# Schematic.net
KiCad netlist of a schematic drawn in EAGLE
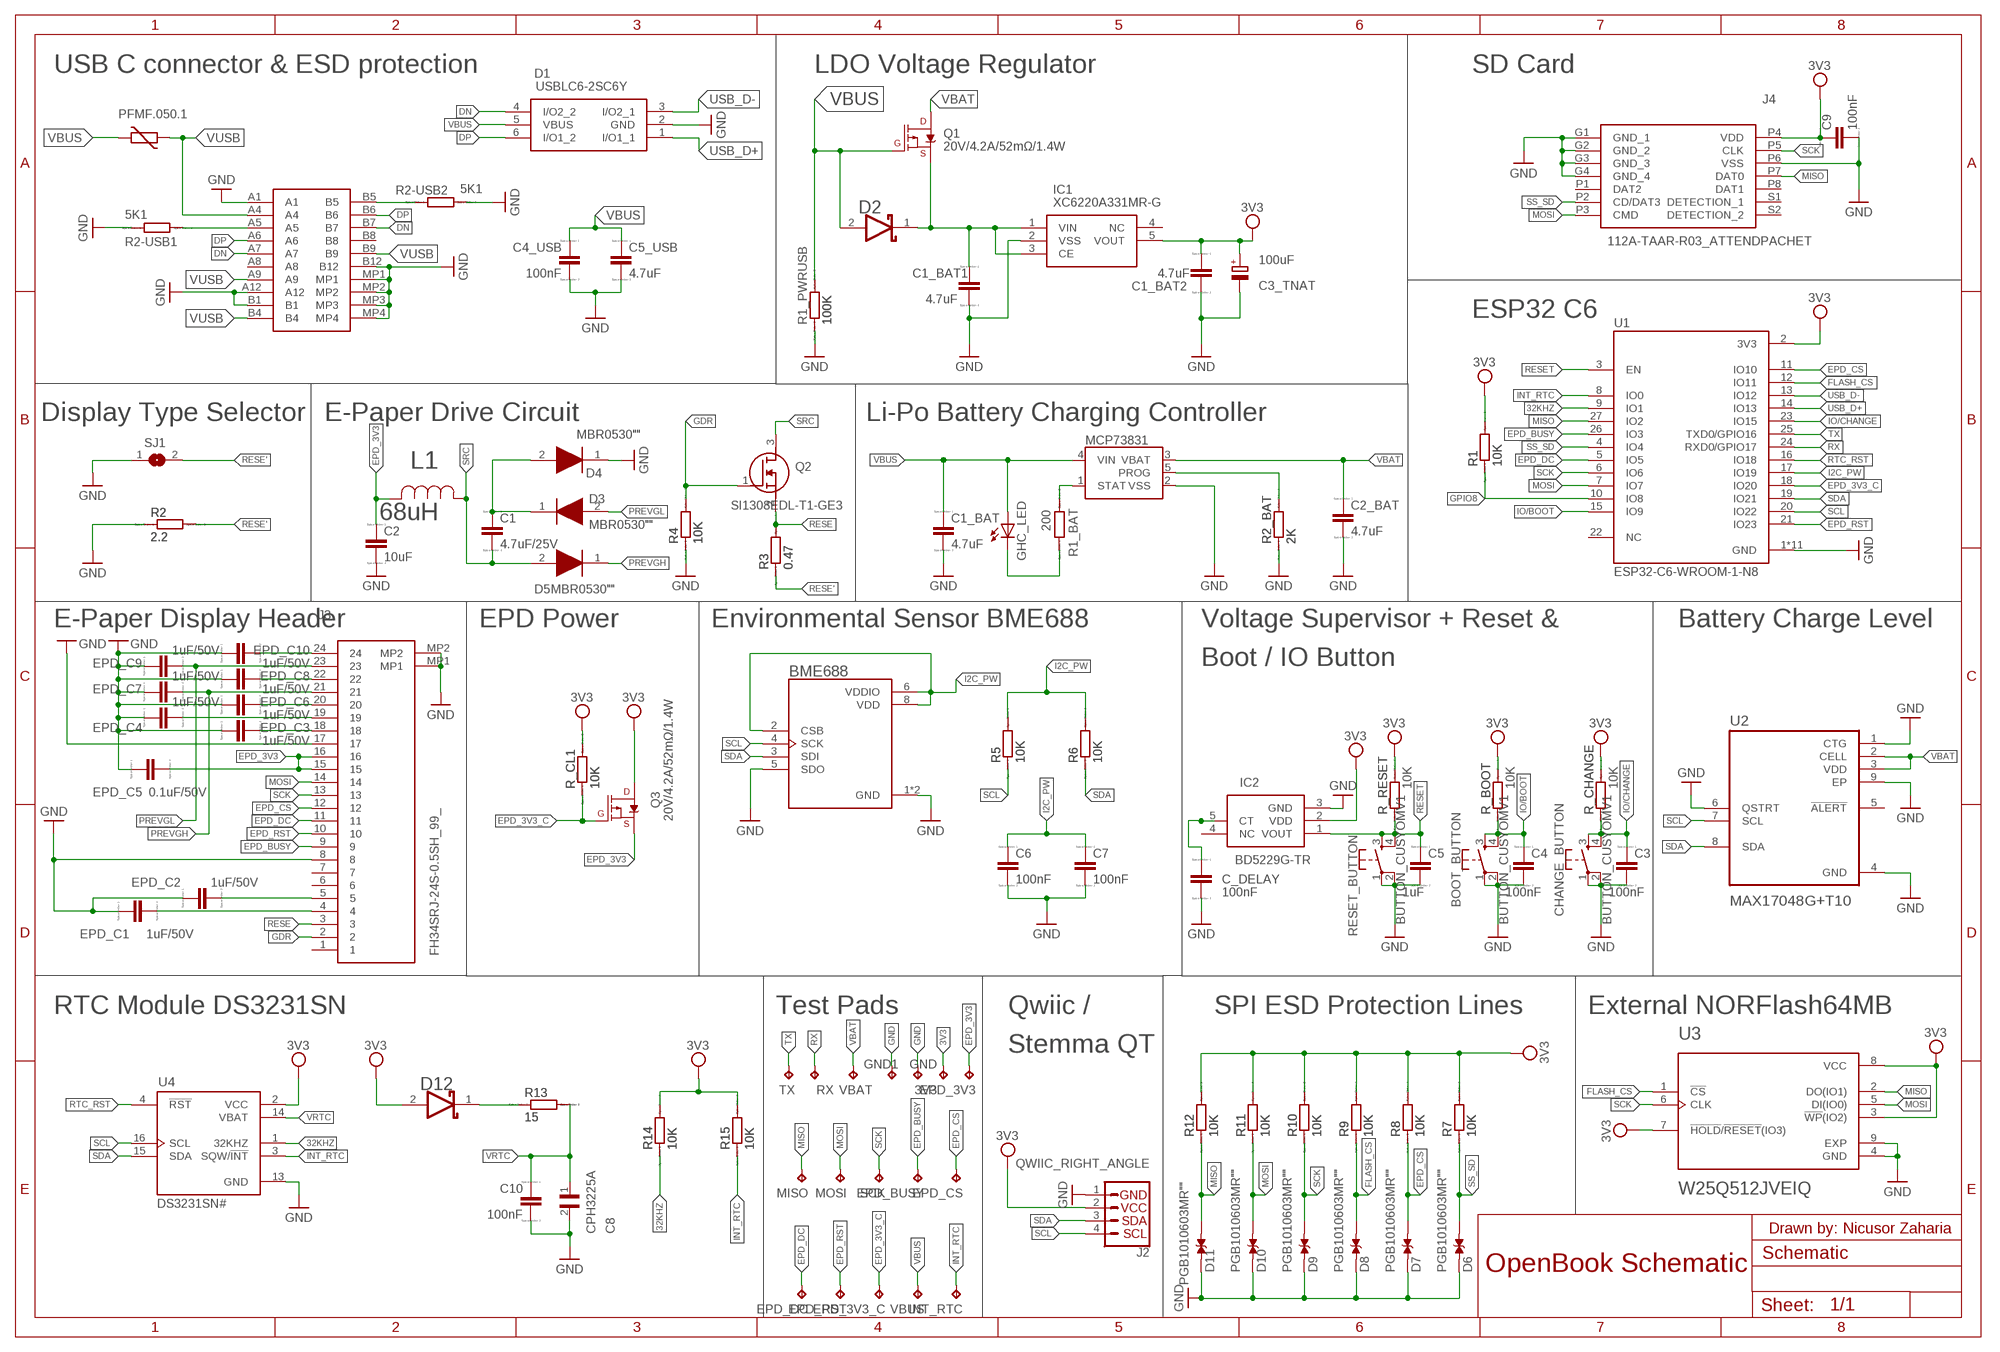
[diagram p0: schematic, sheet 1]

(export (version "E")
  (design (tool "Eeschema 10.0.6"))
  (components
    (comp (ref "3V3")
      (value "TPTP20R")
      (footprint "eagle-import:TP20R")
      (libsource (lib "eagle-import") (part "TPTP20R"))
    )
    (comp (ref "BME688")
      (value "ESP32_WROVER_BME680_BME680")
      (footprint "eagle-import:ESP32_WROVER_BME680_PSON80P300X300X100-8N")
      (fields (field (name "MF") "Bosch Sensortec") (field (name "MP") "BME680"))
      (libsource (lib "eagle-import") (part "ESP32_WROVER_BME680_BME680"))
    )
    (comp (ref "BOOT_BUTTON")
      (value "BUTTON_CUSYOMV1")
      (footprint "eagle-import:MYBUTTON")
      (libsource (lib "eagle-import") (part "BUTTON_CUSYOMV1MINE"))
    )
    (comp (ref "C1")
      (value "4.7uF/25V")
      (footprint "eagle-import:EAGLE-LTSPICE_C0402")
      (libsource (lib "eagle-import") (part "EAGLE-LTSPICE_CC0402"))
    )
    (comp (ref "C1_BAT")
      (value "4.7uF")
      (footprint "eagle-import:EAGLE-LTSPICE_C0402")
      (libsource (lib "eagle-import") (part "EAGLE-LTSPICE_CC0402"))
    )
    (comp (ref "C1_BAT1")
      (value "4.7uF")
      (footprint "eagle-import:EAGLE-LTSPICE_C0402")
      (libsource (lib "eagle-import") (part "EAGLE-LTSPICE_CC0402"))
    )
    (comp (ref "C1_BAT2")
      (value "4.7uF")
      (footprint "eagle-import:EAGLE-LTSPICE_C0402")
      (libsource (lib "eagle-import") (part "EAGLE-LTSPICE_CC0402"))
    )
    (comp (ref "C2")
      (value "10uF")
      (footprint "eagle-import:EAGLE-LTSPICE_C0402")
      (libsource (lib "eagle-import") (part "EAGLE-LTSPICE_CC0402"))
    )
    (comp (ref "C2_BAT")
      (value "4.7uF")
      (footprint "eagle-import:EAGLE-LTSPICE_C0402")
      (libsource (lib "eagle-import") (part "EAGLE-LTSPICE_CC0402"))
    )
    (comp (ref "C3")
      (value "100nF")
      (footprint "eagle-import:EAGLE-LTSPICE_C0402")
      (libsource (lib "eagle-import") (part "EAGLE-LTSPICE_CC0402"))
    )
    (comp (ref "C3_TNAT")
      (value "100uF")
      (footprint "eagle-import:RCL_CT3528")
      (libsource (lib "eagle-import") (part "RCL_CPOL-EUCT3528"))
    )
    (comp (ref "C4")
      (value "100nF")
      (footprint "eagle-import:EAGLE-LTSPICE_C0402")
      (libsource (lib "eagle-import") (part "EAGLE-LTSPICE_CC0402"))
    )
    (comp (ref "C4_USB")
      (value "100nF")
      (footprint "eagle-import:EAGLE-LTSPICE_C0402")
      (libsource (lib "eagle-import") (part "EAGLE-LTSPICE_CC0402"))
    )
    (comp (ref "C5")
      (value "1uF")
      (footprint "eagle-import:EAGLE-LTSPICE_C0402")
      (libsource (lib "eagle-import") (part "EAGLE-LTSPICE_CC0402"))
    )
    (comp (ref "C5_USB")
      (value "4.7uF")
      (footprint "eagle-import:EAGLE-LTSPICE_C0402")
      (libsource (lib "eagle-import") (part "EAGLE-LTSPICE_CC0402"))
    )
    (comp (ref "C6")
      (value "100nF")
      (footprint "eagle-import:EAGLE-LTSPICE_C0402")
      (libsource (lib "eagle-import") (part "EAGLE-LTSPICE_CC0402"))
    )
    (comp (ref "C7")
      (value "100nF")
      (footprint "eagle-import:EAGLE-LTSPICE_C0402")
      (libsource (lib "eagle-import") (part "EAGLE-LTSPICE_CC0402"))
    )
    (comp (ref "C8")
      (value "CPH3225A")
      (footprint "eagle-import:CAPCP3225X100N")
      (fields (field (name "MF") "Seiko Instruments"))
      (libsource (lib "eagle-import") (part "CPH3225A"))
    )
    (comp (ref "C9")
      (value "100nF")
      (footprint "eagle-import:EAGLE-LTSPICE_C0402")
      (libsource (lib "eagle-import") (part "EAGLE-LTSPICE_CC0402"))
    )
    (comp (ref "C10")
      (value "100nF")
      (footprint "eagle-import:EAGLE-LTSPICE_C0402")
      (libsource (lib "eagle-import") (part "EAGLE-LTSPICE_CC0402"))
    )
    (comp (ref "CHANGE_BUTTON")
      (value "BUTTON_CUSYOMV1")
      (footprint "eagle-import:MYBUTTON")
      (libsource (lib "eagle-import") (part "BUTTON_CUSYOMV1MINE"))
    )
    (comp (ref "C_DELAY")
      (value "100nF")
      (footprint "eagle-import:EAGLE-LTSPICE_C0402")
      (libsource (lib "eagle-import") (part "EAGLE-LTSPICE_CC0402"))
    )
    (comp (ref "D1")
      (value "USBLC6-2SC6Y")
      (footprint "eagle-import:SOT95P280X145-6N")
      (fields (field (name "MF") "STMicroelectronics"))
      (libsource (lib "eagle-import") (part "USBLC6-2SC6Y"))
    )
    (comp (ref "D2")
      (value "ESP32_WROVER_AVX---SD0805S020S1R0_AVX_SD0805S020S1R0_0_0AVX_SD0805S020S1R0_0_0")
      (footprint "eagle-import:ESP32_WROVER_AVX---SD0805S020S1R0_AVX_SD0805S020S1R0_0")
      (fields
        (field (name "DIGIKEY_PART_NUMBER") "478-7800-1-ND")
        (field (name "MF") "AVX")
        (field (name "MOUSER_PART_NUMBER") "581-SD0805S020S1R0")
      )
      (libsource (lib "eagle-import") (part "ESP32_WROVER_AVX---SD0805S020S1R0_AVX_SD0805S020S1R0_0_0AVX_SD0805S020S1R0_0_0"))
    )
    (comp (ref "D3")
      (value "MBR0530\"\"")
      (footprint "eagle-import:SOD3716X135N")
      (libsource (lib "eagle-import") (part "MBR0530{dblquote}{dblquote}"))
    )
    (comp (ref "D4")
      (value "MBR0530\"\"")
      (footprint "eagle-import:SOD3716X135N")
      (libsource (lib "eagle-import") (part "MBR0530{dblquote}{dblquote}"))
    )
    (comp (ref "D5")
      (value "MBR0530\"\"")
      (footprint "eagle-import:SOD3716X135N")
      (libsource (lib "eagle-import") (part "MBR0530{dblquote}{dblquote}"))
    )
    (comp (ref "D6")
      (value "PGB1010603MR\"\"")
      (footprint "eagle-import:DIOC1608X36N")
      (libsource (lib "eagle-import") (part "PGB1010603MR{dblquote}{dblquote}"))
    )
    (comp (ref "D7")
      (value "PGB1010603MR\"\"")
      (footprint "eagle-import:DIOC1608X36N")
      (libsource (lib "eagle-import") (part "PGB1010603MR{dblquote}{dblquote}"))
    )
    (comp (ref "D8")
      (value "PGB1010603MR\"\"")
      (footprint "eagle-import:DIOC1608X36N")
      (libsource (lib "eagle-import") (part "PGB1010603MR{dblquote}{dblquote}"))
    )
    (comp (ref "D9")
      (value "PGB1010603MR\"\"")
      (footprint "eagle-import:DIOC1608X36N")
      (libsource (lib "eagle-import") (part "PGB1010603MR{dblquote}{dblquote}"))
    )
    (comp (ref "D10")
      (value "PGB1010603MR\"\"")
      (footprint "eagle-import:DIOC1608X36N")
      (libsource (lib "eagle-import") (part "PGB1010603MR{dblquote}{dblquote}"))
    )
    (comp (ref "D11")
      (value "PGB1010603MR\"\"")
      (footprint "eagle-import:DIOC1608X36N")
      (libsource (lib "eagle-import") (part "PGB1010603MR{dblquote}{dblquote}"))
    )
    (comp (ref "D12")
      (value "ESP32_WROVER_AVX---SD0805S020S1R0_AVX_SD0805S020S1R0_0_0AVX_SD0805S020S1R0_0_0")
      (footprint "eagle-import:ESP32_WROVER_AVX---SD0805S020S1R0_AVX_SD0805S020S1R0_0")
      (fields
        (field (name "DIGIKEY_PART_NUMBER") "478-7800-1-ND")
        (field (name "MF") "AVX")
        (field (name "MOUSER_PART_NUMBER") "581-SD0805S020S1R0")
      )
      (libsource (lib "eagle-import") (part "ESP32_WROVER_AVX---SD0805S020S1R0_AVX_SD0805S020S1R0_0_0AVX_SD0805S020S1R0_0_0"))
    )
    (comp (ref "EPD_3V3")
      (value "TPTP20R")
      (footprint "eagle-import:TP20R")
      (libsource (lib "eagle-import") (part "TPTP20R"))
    )
    (comp (ref "EPD_3V3_C")
      (value "TPTP20R")
      (footprint "eagle-import:TP20R")
      (libsource (lib "eagle-import") (part "TPTP20R"))
    )
    (comp (ref "EPD_BUSY")
      (value "TPTP20R")
      (footprint "eagle-import:TP20R")
      (libsource (lib "eagle-import") (part "TPTP20R"))
    )
    (comp (ref "EPD_C1")
      (value "1uF/50V")
      (footprint "eagle-import:EAGLE-LTSPICE_C0402")
      (libsource (lib "eagle-import") (part "EAGLE-LTSPICE_CC0402"))
    )
    (comp (ref "EPD_C2")
      (value "1uF/50V")
      (footprint "eagle-import:EAGLE-LTSPICE_C0402")
      (libsource (lib "eagle-import") (part "EAGLE-LTSPICE_CC0402"))
    )
    (comp (ref "EPD_C3")
      (value "1uF/50V")
      (footprint "eagle-import:EAGLE-LTSPICE_C0402")
      (libsource (lib "eagle-import") (part "EAGLE-LTSPICE_CC0402"))
    )
    (comp (ref "EPD_C4")
      (value "1uF/50V")
      (footprint "eagle-import:EAGLE-LTSPICE_C0402")
      (libsource (lib "eagle-import") (part "EAGLE-LTSPICE_CC0402"))
    )
    (comp (ref "EPD_C5")
      (value "0.1uF/50V")
      (footprint "eagle-import:EAGLE-LTSPICE_C0402")
      (libsource (lib "eagle-import") (part "EAGLE-LTSPICE_CC0402"))
    )
    (comp (ref "EPD_C6")
      (value "1uF/50V")
      (footprint "eagle-import:EAGLE-LTSPICE_C0402")
      (libsource (lib "eagle-import") (part "EAGLE-LTSPICE_CC0402"))
    )
    (comp (ref "EPD_C7")
      (value "1uF/50V")
      (footprint "eagle-import:EAGLE-LTSPICE_C0402")
      (libsource (lib "eagle-import") (part "EAGLE-LTSPICE_CC0402"))
    )
    (comp (ref "EPD_C8")
      (value "1uF/50V")
      (footprint "eagle-import:EAGLE-LTSPICE_C0402")
      (libsource (lib "eagle-import") (part "EAGLE-LTSPICE_CC0402"))
    )
    (comp (ref "EPD_C9")
      (value "1uF/50V")
      (footprint "eagle-import:EAGLE-LTSPICE_C0402")
      (libsource (lib "eagle-import") (part "EAGLE-LTSPICE_CC0402"))
    )
    (comp (ref "EPD_C10")
      (value "1uF/50V")
      (footprint "eagle-import:EAGLE-LTSPICE_C0402")
      (libsource (lib "eagle-import") (part "EAGLE-LTSPICE_CC0402"))
    )
    (comp (ref "EPD_CS")
      (value "TPTP20R")
      (footprint "eagle-import:TP20R")
      (libsource (lib "eagle-import") (part "TPTP20R"))
    )
    (comp (ref "EPD_DC")
      (value "TPTP20R")
      (footprint "eagle-import:TP20R")
      (libsource (lib "eagle-import") (part "TPTP20R"))
    )
    (comp (ref "EPD_RST")
      (value "TPTP20R")
      (footprint "eagle-import:TP20R")
      (libsource (lib "eagle-import") (part "TPTP20R"))
    )
    (comp (ref "GHC_LED")
      (value "ADAFRUIT_LEDCHIP-LED0603")
      (footprint "eagle-import:ADAFRUIT_CHIP-LED0603")
      (libsource (lib "eagle-import") (part "ADAFRUIT_LEDCHIP-LED0603"))
    )
    (comp (ref "GND")
      (value "TPTP20R")
      (footprint "eagle-import:TP20R")
      (libsource (lib "eagle-import") (part "TPTP20R"))
    )
    (comp (ref "GND1")
      (value "TPTP20R")
      (footprint "eagle-import:TP20R")
      (libsource (lib "eagle-import") (part "TPTP20R"))
    )
    (comp (ref "IC1")
      (value "XC6220A331MR-G")
      (footprint "eagle-import:SOT95P280X120-5N")
      (fields (field (name "MOUSER_PART_NUMBER") "865-XC6220A331MR-G"))
      (libsource (lib "eagle-import") (part "XC6220A331MR-G"))
    )
    (comp (ref "IC2")
      (value "BD5229G-TR")
      (footprint "eagle-import:SOT95P280X125-5N")
      (fields (field (name "MOUSER_PART_NUMBER") "755-BD5229G-TR"))
      (libsource (lib "eagle-import") (part "BD5229G-TR"))
    )
    (comp (ref "INT_RTC")
      (value "TPTP20R")
      (footprint "eagle-import:TP20R")
      (libsource (lib "eagle-import") (part "TPTP20R"))
    )
    (comp (ref "J1")
      (value "SAMACSYS_PARTS_USB4110-GF-A")
      (footprint "eagle-import:SAMACSYS_PARTS_USB4110GFA")
      (fields
        (field (name "MANUFACTURER_PART_NUMBER") "USB4110-GF-A")
        (field (name "MOUSER_PART_NUMBER") "640-USB4110-GF-A")
      )
      (libsource (lib "eagle-import") (part "SAMACSYS_PARTS_USB4110-GF-A"))
    )
    (comp (ref "J2")
      (value "QWIIC_RIGHT_ANGLE")
      (footprint "eagle-import:JST04_1MM_RA")
      (libsource (lib "eagle-import") (part "QWIIC_CONNECTORJS-1MM"))
    )
    (comp (ref "J3")
      (value "FH34SRJ-24S-0.5SH_99_")
      (footprint "eagle-import:FH34SRJ24S05SH99")
      (fields
        (field (name "MANUFACTURER_PART_NUMBER") "FH34SRJ-24S-0.5SH(99)")
        (field (name "MOUSER_PART_NUMBER") "798-FH34SRJ24S05SH99")
      )
      (libsource (lib "eagle-import") (part "FH34SRJ-24S-0.5SH_99_"))
    )
    (comp (ref "J4")
      (value "112A-TAAR-R03_ATTENDPACHET")
      (footprint "eagle-import:112ATAARR03ATTEND")
      (libsource (lib "eagle-import") (part "112A-TAAR-R03_ATTENDPACHET"))
    )
    (comp (ref "L1")
      (value "68uH")
      (footprint "eagle-import:IND_4828-WE-TPC_WRE")
      (fields
        (field (name "MANUFACTURER_PART_NUMBER") "744043680")
        (field (name "COPYRIGHT") "Copyright (C) 2024 Ultra Librarian. All rights reserved.")
      )
      (libsource (lib "eagle-import") (part "744043680IND_4828-WE-TPC_WRE"))
    )
    (comp (ref "MCP73831")
      (value "ESP32_WROVER_SPARKFUN-IC-POWER_MCP73831")
      (footprint "eagle-import:ESP32_WROVER_SPARKFUN-IC-POWER_SOT23-5")
      (libsource (lib "eagle-import") (part "ESP32_WROVER_SPARKFUN-IC-POWER_MCP73831"))
    )
    (comp (ref "MISO")
      (value "TPTP20R")
      (footprint "eagle-import:TP20R")
      (libsource (lib "eagle-import") (part "TPTP20R"))
    )
    (comp (ref "MOSI")
      (value "TPTP20R")
      (footprint "eagle-import:TP20R")
      (libsource (lib "eagle-import") (part "TPTP20R"))
    )
    (comp (ref "PFMF.050.1")
      (value "ESP32C6_VARISTORCN1812")
      (footprint "eagle-import:ESP32C6_VARISTOR_CT_CN1812")
      (libsource (lib "eagle-import") (part "ESP32C6_VARISTORCN1812"))
    )
    (comp (ref "Q1")
      (value "20V/4.2A/52mΩ/1.4W")
      (footprint "eagle-import:ESP32_WROVER_SPARKFUN-DISCRETESEMI_SOT23-3")
      (libsource (lib "eagle-import") (part "ESP32_WROVER_SPARKFUN-DISCRETESEMI_MOSFET_PCH-DMG2305UX-7"))
    )
    (comp (ref "Q2")
      (value "SI1308EDL-T1-GE3")
      (footprint "eagle-import:SOT65P210X110-3N")
      (fields (field (name "MF") "Vishay Siliconix"))
      (libsource (lib "eagle-import") (part "SI1308EDL-T1-GE3"))
    )
    (comp (ref "Q3")
      (value "20V/4.2A/52mΩ/1.4W")
      (footprint "eagle-import:ESP32_WROVER_SPARKFUN-DISCRETESEMI_SOT23-3")
      (libsource (lib "eagle-import") (part "ESP32_WROVER_SPARKFUN-DISCRETESEMI_MOSFET_PCH-DMG2305UX-7"))
    )
    (comp (ref "R1")
      (value "10K")
      (footprint "eagle-import:ESP32_WROVER_EAGLE-LTSPICE_R0402")
      (libsource (lib "eagle-import") (part "ESP32_WROVER_EAGLE-LTSPICE_R"))
    )
    (comp (ref "R1_BAT")
      (value "200")
      (footprint "eagle-import:ESP32_WROVER_EAGLE-LTSPICE_R0402")
      (libsource (lib "eagle-import") (part "ESP32_WROVER_EAGLE-LTSPICE_R"))
    )
    (comp (ref "R1_PWRUSB")
      (value "100K")
      (footprint "eagle-import:ESP32_WROVER_EAGLE-LTSPICE_R0402")
      (libsource (lib "eagle-import") (part "ESP32_WROVER_EAGLE-LTSPICE_R"))
    )
    (comp (ref "R2")
      (value "2.2")
      (footprint "eagle-import:ESP32_WROVER_EAGLE-LTSPICE_R0402")
      (libsource (lib "eagle-import") (part "ESP32_WROVER_EAGLE-LTSPICE_R"))
    )
    (comp (ref "R2-USB1")
      (value "5K1")
      (footprint "eagle-import:ESP32_WROVER_EAGLE-LTSPICE_R0402")
      (libsource (lib "eagle-import") (part "ESP32_WROVER_EAGLE-LTSPICE_R"))
    )
    (comp (ref "R2-USB2")
      (value "5K1")
      (footprint "eagle-import:ESP32_WROVER_EAGLE-LTSPICE_R0402")
      (libsource (lib "eagle-import") (part "ESP32_WROVER_EAGLE-LTSPICE_R"))
    )
    (comp (ref "R2_BAT")
      (value "2K")
      (footprint "eagle-import:ESP32_WROVER_EAGLE-LTSPICE_R0402")
      (libsource (lib "eagle-import") (part "ESP32_WROVER_EAGLE-LTSPICE_R"))
    )
    (comp (ref "R3")
      (value "0.47")
      (footprint "eagle-import:ESP32_WROVER_EAGLE-LTSPICE_R0402")
      (libsource (lib "eagle-import") (part "ESP32_WROVER_EAGLE-LTSPICE_R"))
    )
    (comp (ref "R4")
      (value "10K")
      (footprint "eagle-import:ESP32_WROVER_EAGLE-LTSPICE_R0402")
      (libsource (lib "eagle-import") (part "ESP32_WROVER_EAGLE-LTSPICE_R"))
    )
    (comp (ref "R5")
      (value "10K")
      (footprint "eagle-import:ESP32_WROVER_EAGLE-LTSPICE_R0402")
      (libsource (lib "eagle-import") (part "ESP32_WROVER_EAGLE-LTSPICE_R"))
    )
    (comp (ref "R6")
      (value "10K")
      (footprint "eagle-import:ESP32_WROVER_EAGLE-LTSPICE_R0402")
      (libsource (lib "eagle-import") (part "ESP32_WROVER_EAGLE-LTSPICE_R"))
    )
    (comp (ref "R7")
      (value "10K")
      (footprint "eagle-import:ESP32_WROVER_EAGLE-LTSPICE_R0402")
      (libsource (lib "eagle-import") (part "ESP32_WROVER_EAGLE-LTSPICE_R"))
    )
    (comp (ref "R8")
      (value "10K")
      (footprint "eagle-import:ESP32_WROVER_EAGLE-LTSPICE_R0402")
      (libsource (lib "eagle-import") (part "ESP32_WROVER_EAGLE-LTSPICE_R"))
    )
    (comp (ref "R9")
      (value "10K")
      (footprint "eagle-import:ESP32_WROVER_EAGLE-LTSPICE_R0402")
      (libsource (lib "eagle-import") (part "ESP32_WROVER_EAGLE-LTSPICE_R"))
    )
    (comp (ref "R10")
      (value "10K")
      (footprint "eagle-import:ESP32_WROVER_EAGLE-LTSPICE_R0402")
      (libsource (lib "eagle-import") (part "ESP32_WROVER_EAGLE-LTSPICE_R"))
    )
    (comp (ref "R11")
      (value "10K")
      (footprint "eagle-import:ESP32_WROVER_EAGLE-LTSPICE_R0402")
      (libsource (lib "eagle-import") (part "ESP32_WROVER_EAGLE-LTSPICE_R"))
    )
    (comp (ref "R12")
      (value "10K")
      (footprint "eagle-import:ESP32_WROVER_EAGLE-LTSPICE_R0402")
      (libsource (lib "eagle-import") (part "ESP32_WROVER_EAGLE-LTSPICE_R"))
    )
    (comp (ref "R13")
      (value "15")
      (footprint "eagle-import:ESP32_WROVER_EAGLE-LTSPICE_R0402")
      (libsource (lib "eagle-import") (part "ESP32_WROVER_EAGLE-LTSPICE_R"))
    )
    (comp (ref "R14")
      (value "10K")
      (footprint "eagle-import:ESP32_WROVER_EAGLE-LTSPICE_R0402")
      (libsource (lib "eagle-import") (part "ESP32_WROVER_EAGLE-LTSPICE_R"))
    )
    (comp (ref "R15")
      (value "10K")
      (footprint "eagle-import:ESP32_WROVER_EAGLE-LTSPICE_R0402")
      (libsource (lib "eagle-import") (part "ESP32_WROVER_EAGLE-LTSPICE_R"))
    )
    (comp (ref "RESET_BUTTON")
      (value "BUTTON_CUSYOMV1")
      (footprint "eagle-import:MYBUTTON")
      (libsource (lib "eagle-import") (part "BUTTON_CUSYOMV1MINE"))
    )
    (comp (ref "RX")
      (value "TPTP20R")
      (footprint "eagle-import:TP20R")
      (libsource (lib "eagle-import") (part "TPTP20R"))
    )
    (comp (ref "R_BOOT")
      (value "10K")
      (footprint "eagle-import:ESP32_WROVER_EAGLE-LTSPICE_R0402")
      (libsource (lib "eagle-import") (part "ESP32_WROVER_EAGLE-LTSPICE_R"))
    )
    (comp (ref "R_CHANGE")
      (value "10K")
      (footprint "eagle-import:ESP32_WROVER_EAGLE-LTSPICE_R0402")
      (libsource (lib "eagle-import") (part "ESP32_WROVER_EAGLE-LTSPICE_R"))
    )
    (comp (ref "R_CL1")
      (value "10K")
      (footprint "eagle-import:ESP32_WROVER_EAGLE-LTSPICE_R0402")
      (libsource (lib "eagle-import") (part "ESP32_WROVER_EAGLE-LTSPICE_R"))
    )
    (comp (ref "R_RESET")
      (value "10K")
      (footprint "eagle-import:ESP32_WROVER_EAGLE-LTSPICE_R0402")
      (libsource (lib "eagle-import") (part "ESP32_WROVER_EAGLE-LTSPICE_R"))
    )
    (comp (ref "SCK")
      (value "TPTP20R")
      (footprint "eagle-import:TP20R")
      (libsource (lib "eagle-import") (part "TPTP20R"))
    )
    (comp (ref "SJ1") (value "SJ") (footprint "eagle-import:SJ") (libsource (lib "eagle-import") (part "SJ")))
    (comp (ref "TX")
      (value "TPTP20R")
      (footprint "eagle-import:TP20R")
      (libsource (lib "eagle-import") (part "TPTP20R"))
    )
    (comp (ref "U1")
      (value "ESP32-C6-WROOM-1-N8")
      (footprint "eagle-import:XCVR_ESP32-C6-WROOM-1-N8")
      (fields (field (name "MF") "Espressif Systems"))
      (libsource (lib "eagle-import") (part "ESP32-C6-WROOM-1-N8"))
    )
    (comp (ref "U2")
      (value "MAX17048G+T10")
      (footprint "eagle-import:SON50P200X200X80-9N")
      (fields (field (name "MF") "Analog Devices"))
      (libsource (lib "eagle-import") (part "MAX17048G+T10"))
    )
    (comp (ref "U3")
      (value "W25Q512JVEIQ")
      (footprint "eagle-import:SON127P600X800X80-9N")
      (fields (field (name "MF") "Winbond Electronics"))
      (libsource (lib "eagle-import") (part "W25Q512JVEIQ"))
    )
    (comp (ref "U4")
      (value "DS3231SN#")
      (footprint "eagle-import:SOIC127P1032X265-16N")
      (fields (field (name "MF") "Analog Devices"))
      (libsource (lib "eagle-import") (part "DS3231SN#"))
    )
    (comp (ref "VBAT")
      (value "TPTP20R")
      (footprint "eagle-import:TP20R")
      (libsource (lib "eagle-import") (part "TPTP20R"))
    )
    (comp (ref "VBUS")
      (value "TPTP20R")
      (footprint "eagle-import:TP20R")
      (libsource (lib "eagle-import") (part "TPTP20R"))
    )
  )
  (nets
    (net (code "1") (name "3V3") (class "Default")
      (node (ref "3V3") (pin "TP") (pinfunction "TP_TP") (pintype "input"))
      (node (ref "C1_BAT2") (pin "1") (pinfunction "1_1") (pintype "passive"))
      (node (ref "C3_TNAT") (pin "+") (pinfunction "+_+") (pintype "passive"))
      (node (ref "C9") (pin "1") (pinfunction "1_1") (pintype "passive"))
      (node (ref "D12") (pin "2") (pinfunction "ANODE_2") (pintype "bidirectional"))
      (node (ref "IC1") (pin "5") (pinfunction "VOUT_5") (pintype "bidirectional"))
      (node (ref "IC2") (pin "2") (pinfunction "VDD_2") (pintype "bidirectional"))
      (node (ref "J2") (pin "2") (pinfunction "2_2") (pintype "power_in"))
      (node (ref "J4") (pin "P4") (pinfunction "VDD_P4") (pintype "bidirectional"))
      (node (ref "Q3") (pin "3") (pinfunction "D_3") (pintype "bidirectional"))
      (node (ref "R1") (pin "2") (pinfunction "2_2") (pintype "passive"))
      (node (ref "R10") (pin "2") (pinfunction "2_2") (pintype "passive"))
      (node (ref "R11") (pin "2") (pinfunction "2_2") (pintype "passive"))
      (node (ref "R12") (pin "2") (pinfunction "2_2") (pintype "passive"))
      (node (ref "R14") (pin "2") (pinfunction "2_2") (pintype "passive"))
      (node (ref "R15") (pin "2") (pinfunction "2_2") (pintype "passive"))
      (node (ref "R7") (pin "2") (pinfunction "2_2") (pintype "passive"))
      (node (ref "R8") (pin "2") (pinfunction "2_2") (pintype "passive"))
      (node (ref "R9") (pin "2") (pinfunction "2_2") (pintype "passive"))
      (node (ref "R_BOOT") (pin "2") (pinfunction "2_2") (pintype "passive"))
      (node (ref "R_CHANGE") (pin "2") (pinfunction "2_2") (pintype "passive"))
      (node (ref "R_CL1") (pin "2") (pinfunction "2_2") (pintype "passive"))
      (node (ref "R_RESET") (pin "2") (pinfunction "2_2") (pintype "passive"))
      (node (ref "U1") (pin "2") (pinfunction "3V3_2") (pintype "power_in"))
      (node (ref "U3") (pin "3") (pinfunction "~{WP}(IO2)_3") (pintype "bidirectional"))
      (node (ref "U3") (pin "7") (pinfunction "~{HOLD}/~{RESET}(IO3)_7") (pintype "bidirectional"))
      (node (ref "U3") (pin "8") (pinfunction "VCC_8") (pintype "power_in"))
      (node (ref "U4") (pin "2") (pinfunction "VCC_2") (pintype "power_in"))
    )
    (net (code "2") (name "32KHZ") (class "Default")
      (node (ref "R14") (pin "1") (pinfunction "1_1") (pintype "passive"))
      (node (ref "U1") (pin "9") (pinfunction "IO1_9") (pintype "bidirectional"))
      (node (ref "U4") (pin "1") (pinfunction "32KHZ_1") (pintype "output"))
    )
    (net (code "3") (name "DN") (class "Default")
      (node (ref "D1") (pin "4") (pinfunction "I/O2_2_4") (pintype "bidirectional"))
      (node (ref "J1") (pin "A7") (pinfunction "A7_A7") (pintype "bidirectional"))
      (node (ref "J1") (pin "B7") (pinfunction "B7_B7") (pintype "bidirectional"))
    )
    (net (code "4") (name "DP") (class "Default")
      (node (ref "D1") (pin "6") (pinfunction "I/O1_2_6") (pintype "bidirectional"))
      (node (ref "J1") (pin "A6") (pinfunction "A6_A6") (pintype "bidirectional"))
      (node (ref "J1") (pin "B6") (pinfunction "B6_B6") (pintype "bidirectional"))
    )
    (net (code "5") (name "EPD_3V3") (class "Default")
      (node (ref "C2") (pin "1") (pinfunction "1_1") (pintype "passive"))
      (node (ref "EPD_3V3") (pin "TP") (pinfunction "TP_TP") (pintype "input"))
      (node (ref "EPD_C5") (pin "2") (pinfunction "2_2") (pintype "passive"))
      (node (ref "J3") (pin "15") (pinfunction "15_15") (pintype "bidirectional"))
      (node (ref "J3") (pin "16") (pinfunction "16_16") (pintype "bidirectional"))
      (node (ref "L1") (pin "2") (pinfunction "2_2") (pintype "passive"))
      (node (ref "Q3") (pin "2") (pinfunction "S_2") (pintype "bidirectional"))
    )
    (net (code "6") (name "EPD_3V3_C") (class "Default")
      (node (ref "EPD_3V3_C") (pin "TP") (pinfunction "TP_TP") (pintype "input"))
      (node (ref "Q3") (pin "1") (pinfunction "G_1") (pintype "bidirectional"))
      (node (ref "R_CL1") (pin "1") (pinfunction "1_1") (pintype "passive"))
      (node (ref "U1") (pin "18") (pinfunction "IO20_18") (pintype "bidirectional"))
    )
    (net (code "7") (name "EPD_BUSY") (class "Default")
      (node (ref "EPD_BUSY") (pin "TP") (pinfunction "TP_TP") (pintype "input"))
      (node (ref "J3") (pin "9") (pinfunction "9_9") (pintype "bidirectional"))
      (node (ref "U1") (pin "26") (pinfunction "IO3_26") (pintype "bidirectional"))
    )
    (net (code "8") (name "EPD_CS") (class "Default")
      (node (ref "D7") (pin "2") (pinfunction "2_2") (pintype "passive"))
      (node (ref "EPD_CS") (pin "TP") (pinfunction "TP_TP") (pintype "input"))
      (node (ref "J3") (pin "12") (pinfunction "12_12") (pintype "bidirectional"))
      (node (ref "R8") (pin "1") (pinfunction "1_1") (pintype "passive"))
      (node (ref "U1") (pin "11") (pinfunction "IO10_11") (pintype "bidirectional"))
    )
    (net (code "9") (name "EPD_DC") (class "Default")
      (node (ref "EPD_DC") (pin "TP") (pinfunction "TP_TP") (pintype "input"))
      (node (ref "J3") (pin "11") (pinfunction "11_11") (pintype "bidirectional"))
      (node (ref "U1") (pin "5") (pinfunction "IO5_5") (pintype "bidirectional"))
    )
    (net (code "10") (name "EPD_RST") (class "Default")
      (node (ref "EPD_RST") (pin "TP") (pinfunction "TP_TP") (pintype "input"))
      (node (ref "J3") (pin "10") (pinfunction "10_10") (pintype "bidirectional"))
      (node (ref "U1") (pin "21") (pinfunction "IO23_21") (pintype "bidirectional"))
    )
    (net (code "11") (name "FLASH_CS") (class "Default")
      (node (ref "D8") (pin "2") (pinfunction "2_2") (pintype "passive"))
      (node (ref "R9") (pin "1") (pinfunction "1_1") (pintype "passive"))
      (node (ref "U1") (pin "12") (pinfunction "IO11_12") (pintype "bidirectional"))
      (node (ref "U3") (pin "1") (pinfunction "~{CS}_1") (pintype "input"))
    )
    (net (code "12") (name "GDR") (class "Default")
      (node (ref "J3") (pin "2") (pinfunction "2_2") (pintype "bidirectional"))
      (node (ref "Q2") (pin "1") (pinfunction "G_1") (pintype "bidirectional"))
      (node (ref "R4") (pin "2") (pinfunction "2_2") (pintype "passive"))
    )
    (net (code "13") (name "GND") (class "Default")
      (node (ref "BME688") (pin "1") (pinfunction "GND_1") (pintype "power_in"))
      (node (ref "BME688") (pin "5") (pinfunction "SDO_5") (pintype "bidirectional"))
      (node (ref "BME688") (pin "7") (pinfunction "GND_7") (pintype "power_in"))
      (node (ref "BOOT_BUTTON") (pin "1") (pinfunction "1_1") (pintype "passive"))
      (node (ref "BOOT_BUTTON") (pin "2") (pinfunction "2_2") (pintype "passive"))
      (node (ref "C10") (pin "2") (pinfunction "2_2") (pintype "passive"))
      (node (ref "C1_BAT") (pin "2") (pinfunction "2_2") (pintype "passive"))
      (node (ref "C1_BAT1") (pin "2") (pinfunction "2_2") (pintype "passive"))
      (node (ref "C1_BAT2") (pin "2") (pinfunction "2_2") (pintype "passive"))
      (node (ref "C2") (pin "2") (pinfunction "2_2") (pintype "passive"))
      (node (ref "C2_BAT") (pin "2") (pinfunction "2_2") (pintype "passive"))
      (node (ref "C3") (pin "2") (pinfunction "2_2") (pintype "passive"))
      (node (ref "C3_TNAT") (pin "-") (pinfunction "-_-") (pintype "passive"))
      (node (ref "C4") (pin "2") (pinfunction "2_2") (pintype "passive"))
      (node (ref "C4_USB") (pin "2") (pinfunction "2_2") (pintype "passive"))
      (node (ref "C5") (pin "2") (pinfunction "2_2") (pintype "passive"))
      (node (ref "C5_USB") (pin "2") (pinfunction "2_2") (pintype "passive"))
      (node (ref "C6") (pin "2") (pinfunction "2_2") (pintype "passive"))
      (node (ref "C7") (pin "2") (pinfunction "2_2") (pintype "passive"))
      (node (ref "C8") (pin "2") (pinfunction "2_2") (pintype "passive"))
      (node (ref "C9") (pin "2") (pinfunction "2_2") (pintype "passive"))
      (node (ref "CHANGE_BUTTON") (pin "1") (pinfunction "1_1") (pintype "passive"))
      (node (ref "CHANGE_BUTTON") (pin "2") (pinfunction "2_2") (pintype "passive"))
      (node (ref "C_DELAY") (pin "2") (pinfunction "2_2") (pintype "passive"))
      (node (ref "D1") (pin "2") (pinfunction "GND_2") (pintype "bidirectional"))
      (node (ref "D10") (pin "1") (pinfunction "1_1") (pintype "passive"))
      (node (ref "D11") (pin "1") (pinfunction "1_1") (pintype "passive"))
      (node (ref "D4") (pin "1") (pinfunction "K_1") (pintype "bidirectional"))
      (node (ref "D6") (pin "1") (pinfunction "1_1") (pintype "passive"))
      (node (ref "D7") (pin "1") (pinfunction "1_1") (pintype "passive"))
      (node (ref "D8") (pin "1") (pinfunction "1_1") (pintype "passive"))
      (node (ref "D9") (pin "1") (pinfunction "1_1") (pintype "passive"))
      (node (ref "EPD_C1") (pin "1") (pinfunction "1_1") (pintype "passive"))
      (node (ref "EPD_C10") (pin "1") (pinfunction "1_1") (pintype "passive"))
      (node (ref "EPD_C2") (pin "1") (pinfunction "1_1") (pintype "passive"))
      (node (ref "EPD_C3") (pin "1") (pinfunction "1_1") (pintype "passive"))
      (node (ref "EPD_C4") (pin "1") (pinfunction "1_1") (pintype "passive"))
      (node (ref "EPD_C5") (pin "1") (pinfunction "1_1") (pintype "passive"))
      (node (ref "EPD_C6") (pin "1") (pinfunction "1_1") (pintype "passive"))
      (node (ref "EPD_C7") (pin "1") (pinfunction "1_1") (pintype "passive"))
      (node (ref "EPD_C8") (pin "1") (pinfunction "1_1") (pintype "passive"))
      (node (ref "EPD_C9") (pin "1") (pinfunction "1_1") (pintype "passive"))
      (node (ref "GND") (pin "TP") (pinfunction "TP_TP") (pintype "input"))
      (node (ref "GND1") (pin "TP") (pinfunction "TP_TP") (pintype "input"))
      (node (ref "IC1") (pin "2") (pinfunction "VSS_2") (pintype "bidirectional"))
      (node (ref "IC2") (pin "3") (pinfunction "GND_3") (pintype "bidirectional"))
      (node (ref "J1") (pin "A1") (pinfunction "A1_A1") (pintype "bidirectional"))
      (node (ref "J1") (pin "A12") (pinfunction "A12_A12") (pintype "bidirectional"))
      (node (ref "J1") (pin "B1") (pinfunction "B1_B1") (pintype "bidirectional"))
      (node (ref "J1") (pin "B12") (pinfunction "B12_B12") (pintype "bidirectional"))
      (node (ref "J1") (pin "MP1") (pinfunction "MP1_MP1") (pintype "bidirectional"))
      (node (ref "J1") (pin "MP2") (pinfunction "MP2_MP2") (pintype "bidirectional"))
      (node (ref "J1") (pin "MP3") (pinfunction "MP3_MP3") (pintype "bidirectional"))
      (node (ref "J1") (pin "MP4") (pinfunction "MP4_MP4") (pintype "bidirectional"))
      (node (ref "J2") (pin "1") (pinfunction "1_1") (pintype "power_in"))
      (node (ref "J3") (pin "17") (pinfunction "17_17") (pintype "bidirectional"))
      (node (ref "J3") (pin "8") (pinfunction "8_8") (pintype "bidirectional"))
      (node (ref "J3") (pin "MP1") (pinfunction "MP1_MP1") (pintype "bidirectional"))
      (node (ref "J3") (pin "MP2") (pinfunction "MP2_MP2") (pintype "bidirectional"))
      (node (ref "J4") (pin "G1") (pinfunction "GND_1_G1") (pintype "bidirectional"))
      (node (ref "J4") (pin "G2") (pinfunction "GND_2_G2") (pintype "bidirectional"))
      (node (ref "J4") (pin "G3") (pinfunction "GND_3_G3") (pintype "bidirectional"))
      (node (ref "J4") (pin "G4") (pinfunction "GND_4_G4") (pintype "bidirectional"))
      (node (ref "J4") (pin "P6") (pinfunction "VSS_P6") (pintype "bidirectional"))
      (node (ref "MCP73831") (pin "2") (pinfunction "VSS_2") (pintype "power_in"))
      (node (ref "R1_PWRUSB") (pin "1") (pinfunction "1_1") (pintype "passive"))
      (node (ref "R2") (pin "1") (pinfunction "1_1") (pintype "passive"))
      (node (ref "R2-USB1") (pin "1") (pinfunction "1_1") (pintype "passive"))
      (node (ref "R2-USB2") (pin "2") (pinfunction "2_2") (pintype "passive"))
      (node (ref "R2_BAT") (pin "1") (pinfunction "1_1") (pintype "passive"))
      (node (ref "R4") (pin "1") (pinfunction "1_1") (pintype "passive"))
      (node (ref "RESET_BUTTON") (pin "1") (pinfunction "1_1") (pintype "passive"))
      (node (ref "RESET_BUTTON") (pin "2") (pinfunction "2_2") (pintype "passive"))
      (node (ref "SJ1") (pin "1") (pinfunction "1_1") (pintype "passive"))
      (node (ref "U1") (pin "1") (pinfunction "GND_1") (pintype "power_in"))
      (node (ref "U1") (pin "28") (pinfunction "GND_28") (pintype "power_in"))
      (node (ref "U1") (pin "29_1") (pinfunction "GND_29_1") (pintype "power_in"))
      (node (ref "U1") (pin "29_2") (pinfunction "GND_29_2") (pintype "power_in"))
      (node (ref "U1") (pin "29_3") (pinfunction "GND_29_3") (pintype "power_in"))
      (node (ref "U1") (pin "29_4") (pinfunction "GND_29_4") (pintype "power_in"))
      (node (ref "U1") (pin "29_5") (pinfunction "GND_29_5") (pintype "power_in"))
      (node (ref "U1") (pin "29_6") (pinfunction "GND_29_6") (pintype "power_in"))
      (node (ref "U1") (pin "29_7") (pinfunction "GND_29_7") (pintype "power_in"))
      (node (ref "U1") (pin "29_8") (pinfunction "GND_29_8") (pintype "power_in"))
      (node (ref "U1") (pin "29_9") (pinfunction "GND_29_9") (pintype "power_in"))
      (node (ref "U2") (pin "1") (pinfunction "CTG_1") (pintype "power_in"))
      (node (ref "U2") (pin "4") (pinfunction "GND_4") (pintype "power_in"))
      (node (ref "U2") (pin "6") (pinfunction "QSTRT_6") (pintype "input"))
      (node (ref "U2") (pin "9") (pinfunction "EP_9") (pintype "power_in"))
      (node (ref "U3") (pin "4") (pinfunction "GND_4") (pintype "power_in"))
      (node (ref "U3") (pin "9") (pinfunction "EXP_9") (pintype "passive"))
      (node (ref "U4") (pin "13") (pinfunction "GND_13") (pintype "power_in"))
    )
    (net (code "14") (name "GPIO8") (class "Default")
      (node (ref "R1") (pin "1") (pinfunction "1_1") (pintype "passive"))
      (node (ref "U1") (pin "10") (pinfunction "IO8_10") (pintype "bidirectional"))
    )
    (net (code "15") (name "I2C_PW") (class "Default")
      (node (ref "BME688") (pin "2") (pinfunction "CSB_2") (pintype "input"))
      (node (ref "BME688") (pin "6") (pinfunction "VDDIO_6") (pintype "power_in"))
      (node (ref "BME688") (pin "8") (pinfunction "VDD_8") (pintype "power_in"))
      (node (ref "C6") (pin "1") (pinfunction "1_1") (pintype "passive"))
      (node (ref "C7") (pin "1") (pinfunction "1_1") (pintype "passive"))
      (node (ref "R5") (pin "2") (pinfunction "2_2") (pintype "passive"))
      (node (ref "R6") (pin "2") (pinfunction "2_2") (pintype "passive"))
      (node (ref "U1") (pin "17") (pinfunction "IO19_17") (pintype "bidirectional"))
    )
    (net (code "16") (name "INT_RTC") (class "Default")
      (node (ref "INT_RTC") (pin "TP") (pinfunction "TP_TP") (pintype "input"))
      (node (ref "R15") (pin "1") (pinfunction "1_1") (pintype "passive"))
      (node (ref "U1") (pin "8") (pinfunction "IO0_8") (pintype "bidirectional"))
      (node (ref "U4") (pin "3") (pinfunction "SQW/~{INT}_3") (pintype "output"))
    )
    (net (code "17") (name "IO{slash}BOOT") (class "Default")
      (node (ref "BOOT_BUTTON") (pin "3") (pinfunction "3_3") (pintype "passive"))
      (node (ref "BOOT_BUTTON") (pin "4") (pinfunction "4_4") (pintype "passive"))
      (node (ref "C4") (pin "1") (pinfunction "1_1") (pintype "passive"))
      (node (ref "R_BOOT") (pin "1") (pinfunction "1_1") (pintype "passive"))
      (node (ref "U1") (pin "15") (pinfunction "IO9_15") (pintype "bidirectional"))
    )
    (net (code "18") (name "IO{slash}CHANGE") (class "Default")
      (node (ref "C3") (pin "1") (pinfunction "1_1") (pintype "passive"))
      (node (ref "CHANGE_BUTTON") (pin "3") (pinfunction "3_3") (pintype "passive"))
      (node (ref "CHANGE_BUTTON") (pin "4") (pinfunction "4_4") (pintype "passive"))
      (node (ref "R_CHANGE") (pin "1") (pinfunction "1_1") (pintype "passive"))
      (node (ref "U1") (pin "23") (pinfunction "IO15_23") (pintype "bidirectional"))
    )
    (net (code "19") (name "MISO") (class "Default")
      (node (ref "D11") (pin "2") (pinfunction "2_2") (pintype "passive"))
      (node (ref "J4") (pin "P7") (pinfunction "DAT0_P7") (pintype "bidirectional"))
      (node (ref "MISO") (pin "TP") (pinfunction "TP_TP") (pintype "input"))
      (node (ref "R12") (pin "1") (pinfunction "1_1") (pintype "passive"))
      (node (ref "U1") (pin "27") (pinfunction "IO2_27") (pintype "bidirectional"))
      (node (ref "U3") (pin "2") (pinfunction "DO(IO1)_2") (pintype "bidirectional"))
    )
    (net (code "20") (name "MOSI") (class "Default")
      (node (ref "D10") (pin "2") (pinfunction "2_2") (pintype "passive"))
      (node (ref "J3") (pin "14") (pinfunction "14_14") (pintype "bidirectional"))
      (node (ref "J4") (pin "P3") (pinfunction "CMD_P3") (pintype "bidirectional"))
      (node (ref "MOSI") (pin "TP") (pinfunction "TP_TP") (pintype "input"))
      (node (ref "R11") (pin "1") (pinfunction "1_1") (pintype "passive"))
      (node (ref "U1") (pin "7") (pinfunction "IO7_7") (pintype "bidirectional"))
      (node (ref "U3") (pin "5") (pinfunction "DI(IO0)_5") (pintype "bidirectional"))
    )
    (net (code "21") (name "Net-(D2-CATHODE)") (class "Default")
      (node (ref "C1_BAT1") (pin "1") (pinfunction "1_1") (pintype "passive"))
      (node (ref "D2") (pin "1") (pinfunction "CATHODE_1") (pintype "bidirectional"))
      (node (ref "IC1") (pin "1") (pinfunction "VIN_1") (pintype "bidirectional"))
      (node (ref "IC1") (pin "3") (pinfunction "CE_3") (pintype "bidirectional"))
      (node (ref "Q1") (pin "2") (pinfunction "S_2") (pintype "bidirectional"))
    )
    (net (code "22") (name "Net-(D3-K)") (class "Default")
      (node (ref "C1") (pin "1") (pinfunction "1_1") (pintype "passive"))
      (node (ref "D3") (pin "1") (pinfunction "K_1") (pintype "bidirectional"))
      (node (ref "D4") (pin "2") (pinfunction "A_2") (pintype "bidirectional"))
    )
    (net (code "23") (name "Net-(D12-CATHODE)") (class "Default")
      (node (ref "D12") (pin "1") (pinfunction "CATHODE_1") (pintype "bidirectional"))
      (node (ref "R13") (pin "1") (pinfunction "1_1") (pintype "passive"))
    )
    (net (code "24") (name "Net-(EPD_C1-Pad2)") (class "Default")
      (node (ref "EPD_C1") (pin "2") (pinfunction "2_2") (pintype "passive"))
      (node (ref "J3") (pin "4") (pinfunction "4_4") (pintype "bidirectional"))
    )
    (net (code "25") (name "Net-(EPD_C2-Pad2)") (class "Default")
      (node (ref "EPD_C2") (pin "2") (pinfunction "2_2") (pintype "passive"))
      (node (ref "J3") (pin "5") (pinfunction "5_5") (pintype "bidirectional"))
    )
    (net (code "26") (name "Net-(EPD_C3-Pad2)") (class "Default")
      (node (ref "EPD_C3") (pin "2") (pinfunction "2_2") (pintype "passive"))
      (node (ref "J3") (pin "18") (pinfunction "18_18") (pintype "bidirectional"))
    )
    (net (code "27") (name "Net-(EPD_C4-Pad2)") (class "Default")
      (node (ref "EPD_C4") (pin "2") (pinfunction "2_2") (pintype "passive"))
      (node (ref "J3") (pin "19") (pinfunction "19_19") (pintype "bidirectional"))
    )
    (net (code "28") (name "Net-(EPD_C6-Pad2)") (class "Default")
      (node (ref "EPD_C6") (pin "2") (pinfunction "2_2") (pintype "passive"))
      (node (ref "J3") (pin "20") (pinfunction "20_20") (pintype "bidirectional"))
    )
    (net (code "29") (name "Net-(EPD_C8-Pad2)") (class "Default")
      (node (ref "EPD_C8") (pin "2") (pinfunction "2_2") (pintype "passive"))
      (node (ref "J3") (pin "22") (pinfunction "22_22") (pintype "bidirectional"))
    )
    (net (code "30") (name "Net-(EPD_C10-Pad2)") (class "Default")
      (node (ref "EPD_C10") (pin "2") (pinfunction "2_2") (pintype "passive"))
      (node (ref "J3") (pin "24") (pinfunction "24_24") (pintype "bidirectional"))
    )
    (net (code "31") (name "Net-(GHC_LED-PadC)") (class "Default")
      (node (ref "GHC_LED") (pin "C") (pinfunction "C_C") (pintype "passive"))
      (node (ref "R1_BAT") (pin "1") (pinfunction "1_1") (pintype "passive"))
    )
    (net (code "32") (name "Net-(IC2-CT)") (class "Default")
      (node (ref "C_DELAY") (pin "1") (pinfunction "1_1") (pintype "passive"))
      (node (ref "IC2") (pin "5") (pinfunction "CT_5") (pintype "bidirectional"))
    )
    (net (code "33") (name "Net-(J1-PadA5)") (class "Default")
      (node (ref "J1") (pin "A5") (pinfunction "A5_A5") (pintype "bidirectional"))
      (node (ref "R2-USB1") (pin "2") (pinfunction "2_2") (pintype "passive"))
    )
    (net (code "34") (name "Net-(J1-PadB5)") (class "Default")
      (node (ref "J1") (pin "B5") (pinfunction "B5_B5") (pintype "bidirectional"))
      (node (ref "R2-USB2") (pin "1") (pinfunction "1_1") (pintype "passive"))
    )
    (net (code "35") (name "Net-(MCP73831-PROG)") (class "Default")
      (node (ref "MCP73831") (pin "5") (pinfunction "PROG_5") (pintype "input"))
      (node (ref "R2_BAT") (pin "2") (pinfunction "2_2") (pintype "passive"))
    )
    (net (code "36") (name "Net-(MCP73831-STAT)") (class "Default")
      (node (ref "MCP73831") (pin "1") (pinfunction "STAT_1") (pintype "output"))
      (node (ref "R1_BAT") (pin "2") (pinfunction "2_2") (pintype "passive"))
    )
    (net (code "37") (name "PREVGH") (class "Default")
      (node (ref "D5") (pin "1") (pinfunction "K_1") (pintype "bidirectional"))
      (node (ref "EPD_C7") (pin "2") (pinfunction "2_2") (pintype "passive"))
      (node (ref "J3") (pin "21") (pinfunction "21_21") (pintype "bidirectional"))
    )
    (net (code "38") (name "PREVGL") (class "Default")
      (node (ref "D3") (pin "2") (pinfunction "A_2") (pintype "bidirectional"))
      (node (ref "EPD_C9") (pin "2") (pinfunction "2_2") (pintype "passive"))
      (node (ref "J3") (pin "23") (pinfunction "23_23") (pintype "bidirectional"))
    )
    (net (code "39") (name "RESE") (class "Default")
      (node (ref "J3") (pin "3") (pinfunction "3_3") (pintype "bidirectional"))
      (node (ref "Q2") (pin "2") (pinfunction "S_2") (pintype "bidirectional"))
      (node (ref "R3") (pin "2") (pinfunction "2_2") (pintype "passive"))
    )
    (net (code "40") (name "RESE'") (class "Default")
      (node (ref "R2") (pin "2") (pinfunction "2_2") (pintype "passive"))
      (node (ref "R3") (pin "1") (pinfunction "1_1") (pintype "passive"))
      (node (ref "SJ1") (pin "2") (pinfunction "2_2") (pintype "passive"))
    )
    (net (code "41") (name "RESET") (class "Default")
      (node (ref "C5") (pin "1") (pinfunction "1_1") (pintype "passive"))
      (node (ref "IC2") (pin "1") (pinfunction "VOUT_1") (pintype "bidirectional"))
      (node (ref "RESET_BUTTON") (pin "3") (pinfunction "3_3") (pintype "passive"))
      (node (ref "RESET_BUTTON") (pin "4") (pinfunction "4_4") (pintype "passive"))
      (node (ref "R_RESET") (pin "1") (pinfunction "1_1") (pintype "passive"))
      (node (ref "U1") (pin "3") (pinfunction "EN_3") (pintype "input"))
    )
    (net (code "42") (name "RTC_RST") (class "Default")
      (node (ref "U1") (pin "16") (pinfunction "IO18_16") (pintype "bidirectional"))
      (node (ref "U4") (pin "4") (pinfunction "~{RST}_4") (pintype "input"))
    )
    (net (code "43") (name "RX") (class "Default")
      (node (ref "RX") (pin "TP") (pinfunction "TP_TP") (pintype "input"))
      (node (ref "U1") (pin "24") (pinfunction "RXD0/GPIO17_24") (pintype "bidirectional"))
    )
    (net (code "44") (name "SCK") (class "Default")
      (node (ref "D9") (pin "2") (pinfunction "2_2") (pintype "passive"))
      (node (ref "J3") (pin "13") (pinfunction "13_13") (pintype "bidirectional"))
      (node (ref "J4") (pin "P5") (pinfunction "CLK_P5") (pintype "bidirectional"))
      (node (ref "R10") (pin "1") (pinfunction "1_1") (pintype "passive"))
      (node (ref "SCK") (pin "TP") (pinfunction "TP_TP") (pintype "input"))
      (node (ref "U1") (pin "6") (pinfunction "IO6_6") (pintype "bidirectional"))
      (node (ref "U3") (pin "6") (pinfunction "CLK_6") (pintype "input"))
    )
    (net (code "45") (name "SCL") (class "Default")
      (node (ref "BME688") (pin "4") (pinfunction "SCK_4") (pintype "input"))
      (node (ref "J2") (pin "4") (pinfunction "4_4") (pintype "passive"))
      (node (ref "R5") (pin "1") (pinfunction "1_1") (pintype "passive"))
      (node (ref "U1") (pin "20") (pinfunction "IO22_20") (pintype "bidirectional"))
      (node (ref "U2") (pin "7") (pinfunction "SCL_7") (pintype "input"))
      (node (ref "U4") (pin "16") (pinfunction "SCL_16") (pintype "input"))
    )
    (net (code "46") (name "SDA") (class "Default")
      (node (ref "BME688") (pin "3") (pinfunction "SDI_3") (pintype "bidirectional"))
      (node (ref "J2") (pin "3") (pinfunction "3_3") (pintype "passive"))
      (node (ref "R6") (pin "1") (pinfunction "1_1") (pintype "passive"))
      (node (ref "U1") (pin "19") (pinfunction "IO21_19") (pintype "bidirectional"))
      (node (ref "U2") (pin "8") (pinfunction "SDA_8") (pintype "bidirectional"))
      (node (ref "U4") (pin "15") (pinfunction "SDA_15") (pintype "bidirectional"))
    )
    (net (code "47") (name "SRC") (class "Default")
      (node (ref "C1") (pin "2") (pinfunction "2_2") (pintype "passive"))
      (node (ref "D5") (pin "2") (pinfunction "A_2") (pintype "bidirectional"))
      (node (ref "L1") (pin "1") (pinfunction "1_1") (pintype "passive"))
      (node (ref "Q2") (pin "3") (pinfunction "D_3") (pintype "bidirectional"))
    )
    (net (code "48") (name "SS_SD") (class "Default")
      (node (ref "D6") (pin "2") (pinfunction "2_2") (pintype "passive"))
      (node (ref "J4") (pin "P2") (pinfunction "CD/DAT3_P2") (pintype "bidirectional"))
      (node (ref "R7") (pin "1") (pinfunction "1_1") (pintype "passive"))
      (node (ref "U1") (pin "4") (pinfunction "IO4_4") (pintype "bidirectional"))
    )
    (net (code "49") (name "TX") (class "Default")
      (node (ref "TX") (pin "TP") (pinfunction "TP_TP") (pintype "input"))
      (node (ref "U1") (pin "25") (pinfunction "TXD0/GPIO16_25") (pintype "bidirectional"))
    )
    (net (code "50") (name "USB_D+") (class "Default")
      (node (ref "D1") (pin "1") (pinfunction "I/O1_1_1") (pintype "bidirectional"))
      (node (ref "U1") (pin "14") (pinfunction "IO13_14") (pintype "bidirectional"))
    )
    (net (code "51") (name "USB_D-") (class "Default")
      (node (ref "D1") (pin "3") (pinfunction "I/O2_1_3") (pintype "bidirectional"))
      (node (ref "U1") (pin "13") (pinfunction "IO12_13") (pintype "bidirectional"))
    )
    (net (code "52") (name "VBAT") (class "Default")
      (node (ref "C2_BAT") (pin "1") (pinfunction "1_1") (pintype "passive"))
      (node (ref "MCP73831") (pin "3") (pinfunction "VBAT_3") (pintype "power_in"))
      (node (ref "Q1") (pin "3") (pinfunction "D_3") (pintype "bidirectional"))
      (node (ref "U2") (pin "2") (pinfunction "CELL_2") (pintype "power_in"))
      (node (ref "U2") (pin "3") (pinfunction "VDD_3") (pintype "power_in"))
      (node (ref "VBAT") (pin "TP") (pinfunction "TP_TP") (pintype "input"))
    )
    (net (code "53") (name "VBUS") (class "Default")
      (node (ref "C1_BAT") (pin "1") (pinfunction "1_1") (pintype "passive"))
      (node (ref "C4_USB") (pin "1") (pinfunction "1_1") (pintype "passive"))
      (node (ref "C5_USB") (pin "1") (pinfunction "1_1") (pintype "passive"))
      (node (ref "D1") (pin "5") (pinfunction "VBUS_5") (pintype "bidirectional"))
      (node (ref "D2") (pin "2") (pinfunction "ANODE_2") (pintype "bidirectional"))
      (node (ref "GHC_LED") (pin "A") (pinfunction "A_A") (pintype "passive"))
      (node (ref "MCP73831") (pin "4") (pinfunction "VIN_4") (pintype "power_in"))
      (node (ref "PFMF.050.1") (pin "2") (pinfunction "2_2") (pintype "passive"))
      (node (ref "Q1") (pin "1") (pinfunction "G_1") (pintype "bidirectional"))
      (node (ref "R1_PWRUSB") (pin "2") (pinfunction "2_2") (pintype "passive"))
      (node (ref "VBUS") (pin "TP") (pinfunction "TP_TP") (pintype "input"))
    )
    (net (code "54") (name "VRTC") (class "Default")
      (node (ref "C10") (pin "1") (pinfunction "1_1") (pintype "passive"))
      (node (ref "C8") (pin "1") (pinfunction "1_1") (pintype "passive"))
      (node (ref "R13") (pin "2") (pinfunction "2_2") (pintype "passive"))
      (node (ref "U4") (pin "14") (pinfunction "VBAT_14") (pintype "power_in"))
    )
    (net (code "55") (name "VUSB") (class "Default")
      (node (ref "J1") (pin "A4") (pinfunction "A4_A4") (pintype "bidirectional"))
      (node (ref "J1") (pin "A9") (pinfunction "A9_A9") (pintype "bidirectional"))
      (node (ref "J1") (pin "B4") (pinfunction "B4_B4") (pintype "bidirectional"))
      (node (ref "J1") (pin "B9") (pinfunction "B9_B9") (pintype "bidirectional"))
      (node (ref "PFMF.050.1") (pin "1") (pinfunction "1_1") (pintype "passive"))
    )
    (net (code "56") (name "unconnected-(IC1-NC-Pad4)") (class "Default")
      (node (ref "IC1") (pin "4") (pinfunction "NC_4") (pintype "no_connect"))
    )
    (net (code "57") (name "unconnected-(IC2-NC-Pad4)") (class "Default")
      (node (ref "IC2") (pin "4") (pinfunction "NC_4") (pintype "no_connect"))
    )
    (net (code "58") (name "unconnected-(J1-PadA8)") (class "Default")
      (node (ref "J1") (pin "A8") (pinfunction "A8_A8") (pintype "bidirectional"))
    )
    (net (code "59") (name "unconnected-(J1-PadB8)") (class "Default")
      (node (ref "J1") (pin "B8") (pinfunction "B8_B8") (pintype "bidirectional"))
    )
    (net (code "60") (name "unconnected-(J3-Pad1)") (class "Default")
      (node (ref "J3") (pin "1") (pinfunction "1_1") (pintype "bidirectional"))
    )
    (net (code "61") (name "unconnected-(J3-Pad6)") (class "Default")
      (node (ref "J3") (pin "6") (pinfunction "6_6") (pintype "bidirectional"))
    )
    (net (code "62") (name "unconnected-(J3-Pad7)") (class "Default")
      (node (ref "J3") (pin "7") (pinfunction "7_7") (pintype "bidirectional"))
    )
    (net (code "63") (name "unconnected-(J4-DAT1-PadP8)") (class "Default")
      (node (ref "J4") (pin "P8") (pinfunction "DAT1_P8") (pintype "bidirectional"))
    )
    (net (code "64") (name "unconnected-(J4-DAT2-PadP1)") (class "Default")
      (node (ref "J4") (pin "P1") (pinfunction "DAT2_P1") (pintype "bidirectional"))
    )
    (net (code "65") (name "unconnected-(J4-DETECTION_1-PadS1)") (class "Default")
      (node (ref "J4") (pin "S1") (pinfunction "DETECTION_1_S1") (pintype "bidirectional"))
    )
    (net (code "66") (name "unconnected-(J4-DETECTION_2-PadS2)") (class "Default")
      (node (ref "J4") (pin "S2") (pinfunction "DETECTION_2_S2") (pintype "bidirectional"))
    )
    (net (code "67") (name "unconnected-(U1-NC-Pad22)") (class "Default")
      (node (ref "U1") (pin "22") (pinfunction "NC_22") (pintype "no_connect"))
    )
    (net (code "68") (name "unconnected-(U2-~{ALERT}-Pad5)") (class "Default")
      (node (ref "U2") (pin "5") (pinfunction "~{ALERT}_5") (pintype "output"))
    )
  )
)
